# Project.net
KiCad netlist of a schematic drawn in Altium Designer
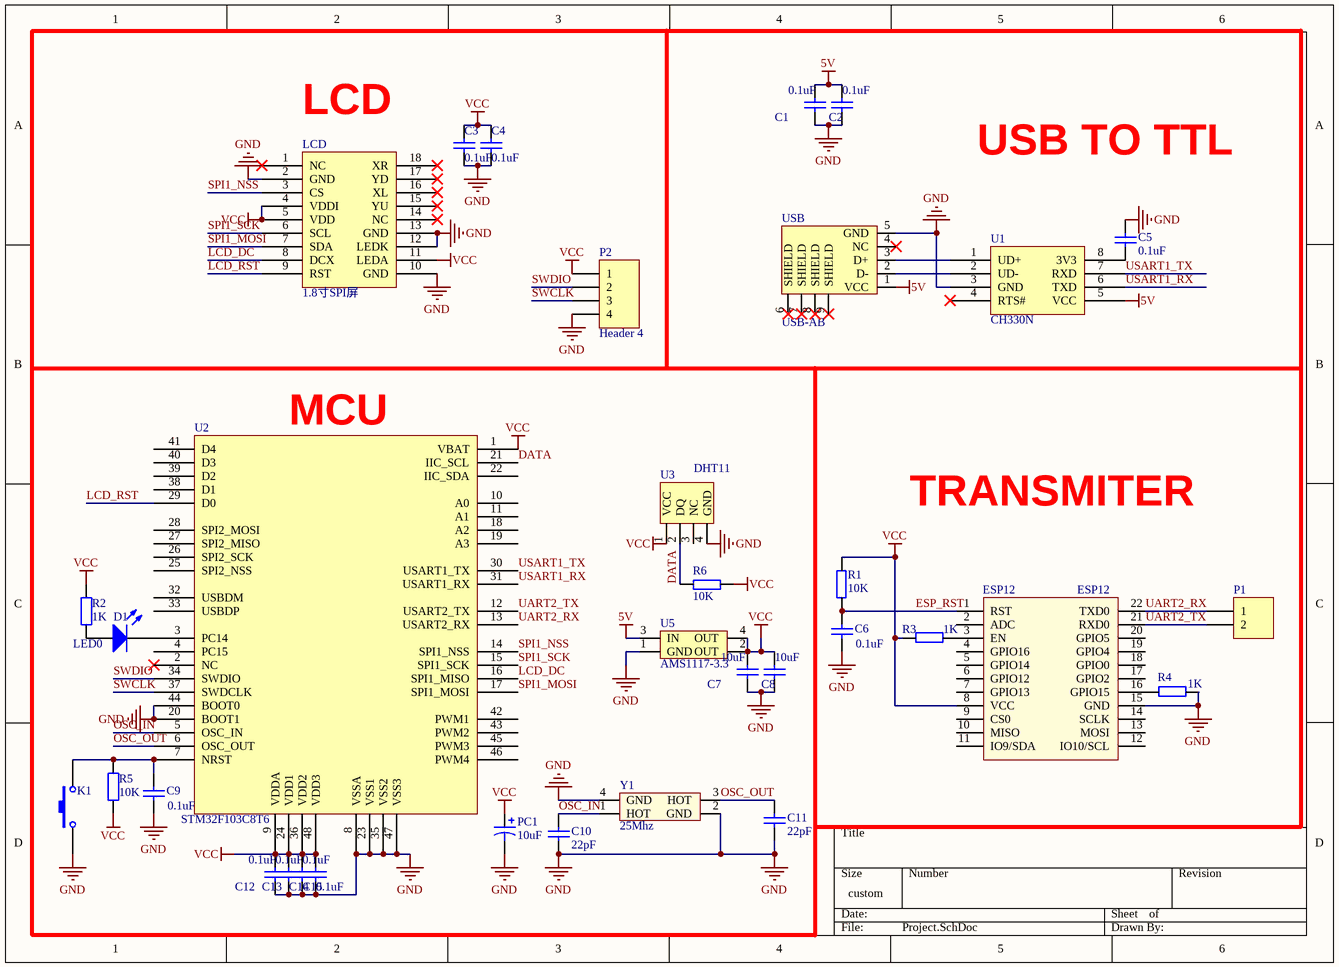
[diagram p0: Project.SchDoc]

(export (version "E")
  (design (tool "Eeschema 10.0.6"))
  (components
    (comp (ref "C1")
      (value "0.1uF")
      (footprint "0603P")
      (description "Capacitor")
      (fields (field (name "Comment") "Cap") (field (name "PUBLISHER") "Altium Limited"))
      (libsource (lib "Miscellaneous Devices") (part "Cap"))
    )
    (comp (ref "C2")
      (value "0.1uF")
      (footprint "0603P")
      (description "Capacitor")
      (fields (field (name "Comment") "Cap") (field (name "PUBLISHER") "Altium Limited"))
      (libsource (lib "Miscellaneous Devices") (part "Cap"))
    )
    (comp (ref "C3")
      (value "0.1uF")
      (footprint "1206")
      (description "Capacitor")
      (fields (field (name "Comment") "Cap") (field (name "PUBLISHER") "Altium Limited"))
      (libsource (lib "Miscellaneous Devices") (part "Cap"))
    )
    (comp (ref "C4")
      (value "0.1uF")
      (footprint "0603P")
      (description "Capacitor")
      (fields (field (name "Comment") "Cap") (field (name "PUBLISHER") "Altium Limited"))
      (libsource (lib "Miscellaneous Devices") (part "Cap"))
    )
    (comp (ref "C5")
      (value "0.1uF")
      (footprint "0603P")
      (description "Capacitor")
      (fields (field (name "Comment") "Cap") (field (name "PUBLISHER") "Altium Limited"))
      (libsource (lib "Miscellaneous Devices") (part "Cap"))
    )
    (comp (ref "C6")
      (value "0.1uF")
      (footprint "0603P")
      (description "Capacitor")
      (fields (field (name "Comment") "Cap") (field (name "PUBLISHER") "Altium Limited"))
      (libsource (lib "Miscellaneous Devices") (part "Cap"))
    )
    (comp (ref "C7")
      (value "10uF")
      (footprint "1206")
      (description "Capacitor")
      (fields (field (name "Comment") "Cap") (field (name "PUBLISHER") "Altium Limited"))
      (libsource (lib "Miscellaneous Devices") (part "Cap"))
    )
    (comp (ref "C8")
      (value "10uF")
      (footprint "1206")
      (description "Capacitor")
      (fields (field (name "Comment") "Cap") (field (name "PUBLISHER") "Altium Limited"))
      (libsource (lib "Miscellaneous Devices") (part "Cap"))
    )
    (comp (ref "C9")
      (value "0.1uF")
      (footprint "0603P")
      (description "Capacitor")
      (fields (field (name "Comment") "Cap") (field (name "PUBLISHER") "Altium Limited"))
      (libsource (lib "Miscellaneous Devices") (part "Cap"))
    )
    (comp (ref "C10")
      (value "22pF")
      (footprint "0603P")
      (description "Capacitor")
      (fields (field (name "Comment") "Cap") (field (name "PUBLISHER") "Altium Limited"))
      (libsource (lib "Miscellaneous Devices") (part "Cap"))
    )
    (comp (ref "C11")
      (value "22pF")
      (footprint "0603P")
      (description "Capacitor")
      (fields (field (name "Comment") "Cap") (field (name "PUBLISHER") "Altium Limited"))
      (libsource (lib "Miscellaneous Devices") (part "Cap"))
    )
    (comp (ref "C12")
      (value "0.1uF")
      (footprint "0603P")
      (description "Capacitor")
      (fields (field (name "Comment") "Cap") (field (name "PUBLISHER") "Altium Limited"))
      (libsource (lib "Miscellaneous Devices") (part "Cap"))
    )
    (comp (ref "C13")
      (value "0.1uF")
      (footprint "0603P")
      (description "Capacitor")
      (fields (field (name "Comment") "Cap") (field (name "PUBLISHER") "Altium Limited"))
      (libsource (lib "Miscellaneous Devices") (part "Cap"))
    )
    (comp (ref "C14")
      (value "0.1uF")
      (footprint "0603P")
      (description "Capacitor")
      (fields (field (name "Comment") "Cap") (field (name "PUBLISHER") "Altium Limited"))
      (libsource (lib "Miscellaneous Devices") (part "Cap"))
    )
    (comp (ref "C15")
      (value "0.1uF")
      (footprint "0603P")
      (description "Capacitor")
      (fields (field (name "Comment") "Cap") (field (name "PUBLISHER") "Altium Limited"))
      (libsource (lib "Miscellaneous Devices") (part "Cap"))
    )
    (comp (ref "D1")
      (value "LED0")
      (footprint "SMDLED-0603")
      (description "Typical INFRARED GaAs LED")
      (fields (field (name "PUBLISHER") "Altium Limited"))
      (libsource (lib "Miscellaneous Devices") (part "LED0"))
    )
    (comp (ref "ESP12")
      (value "ESP12")
      (footprint "ESP-12改后:ESP-12E&F Module")
      (description "ESP-12E&F Module")
      (libsource (lib "ESP-12改后") (part "ESP-12E&F Module"))
    )
    (comp (ref "K1")
      (value "KEY")
      (footprint "KEY_SOP3625")
      (description "Switch")
      (fields (field (name "PUBLISHER") "Altium Limited"))
      (libsource (lib "My Footprint") (part "KEY_2"))
    )
    (comp (ref "LCD")
      (value "1.8寸SPI屏")
      (footprint "FPC0.5 18Pin")
      (libsource (lib "常用元件") (part "1.8寸SPI屏"))
    )
    (comp (ref "P1")
      (value "Header 2")
      (footprint "HDR1X2")
      (description "Header, 2-Pin")
      (fields (field (name "PUBLISHER") "Altium Limited"))
      (libsource (lib "Miscellaneous Connectors") (part "Header 2"))
    )
    (comp (ref "P2")
      (value "Header 4")
      (footprint "HDR1X4")
      (description "Header, 4-Pin")
      (fields (field (name "PUBLISHER") "Altium Limited"))
      (libsource (lib "Miscellaneous Connectors") (part "Header 4"))
    )
    (comp (ref "PC1")
      (value "10uF")
      (footprint "1206")
      (description "Polarized Capacitor (Surface Mount)")
      (fields (field (name "PUBLISHER") "Altium Limited"))
      (libsource (lib "Miscellaneous Devices") (part "Cap Pol3"))
    )
    (comp (ref "R1") (value "10K") (footprint "0603P") (libsource (lib "STM32H743核心板封装库") (part "R")))
    (comp (ref "R2")
      (value "1K")
      (footprint "0603P")
      (description "Resistor")
      (fields (field (name "Comment") "Res2") (field (name "PUBLISHER") "Altium Limited"))
      (libsource (lib "") (part "Res2_1"))
    )
    (comp (ref "R3") (value "1K") (footprint "0603P") (libsource (lib "STM32H743核心板封装库") (part "R")))
    (comp (ref "R4") (value "1K") (footprint "0603P") (libsource (lib "STM32H743核心板封装库") (part "R")))
    (comp (ref "R5")
      (value "10K")
      (footprint "0603P")
      (description "Resistor")
      (fields (field (name "PUBLISHER") "Altium Limited"))
      (libsource (lib "Miscellaneous Devices") (part "Res2"))
    )
    (comp (ref "R6") (value "10K") (footprint "0603P") (libsource (lib "STM32H743核心板封装库") (part "R")))
    (comp (ref "U1") (value "CH330N") (footprint "sop8") (libsource (lib "常用元件") (part "CH330N")))
    (comp (ref "U2")
      (value "STM32F103C8T6")
      (footprint "LQFP-48")
      (libsource (lib "常用元件") (part "STM32F103C8T6"))
    )
    (comp (ref "U3")
      (value "DHT11")
      (footprint "DHT11")
      (description "数字温湿度传感器")
      (libsource (lib "阿波罗STM32F4&F7底板封装库") (part "DHT11"))
    )
    (comp (ref "U5")
      (value "AMS1117-3.3")
      (footprint "AMS1117")
      (libsource (lib "阿波罗STM32F4&F7底板封装库") (part "AMS1117"))
    )
    (comp (ref "USB")
      (value "USB-AB")
      (footprint "USB_AB")
      (description "MicroUSB")
      (libsource (lib "STM32F429核心板封装库") (part "USB-AB"))
    )
    (comp (ref "Y1")
      (value "25Mhz")
      (footprint "XTAL3225")
      (description "3225贴片无源晶振")
      (libsource (lib "STM32F429核心板封装库") (part "XTAL_3225"))
    )
  )
  (nets
    (net (code "1") (name "/DATA") (class "Default")
      (node (ref "R6") (pin "1") (pintype "passive"))
      (node (ref "U2") (pin "21") (pinfunction "IIC_SCL_21") (pintype "passive"))
      (node (ref "U3") (pin "2") (pinfunction "DQ_2") (pintype "passive"))
    )
    (net (code "2") (name "/ESP_RST") (class "Default")
      (node (ref "C6") (pin "2") (pinfunction "2_2") (pintype "passive"))
      (node (ref "ESP12") (pin "1") (pinfunction "RST_1") (pintype "passive"))
      (node (ref "R1") (pin "2") (pintype "passive"))
    )
    (net (code "3") (name "/LCD_DC") (class "Default")
      (node (ref "LCD") (pin "8") (pinfunction "DCX_8") (pintype "passive"))
      (node (ref "U2") (pin "16") (pinfunction "SPI1_MISO_16") (pintype "passive"))
    )
    (net (code "4") (name "/LCD_RST") (class "Default")
      (node (ref "LCD") (pin "9") (pinfunction "RST_9") (pintype "passive"))
      (node (ref "U2") (pin "29") (pinfunction "D0_29") (pintype "passive"))
    )
    (net (code "5") (name "/OSC_IN") (class "Default")
      (node (ref "C10") (pin "1") (pinfunction "1_1") (pintype "passive"))
      (node (ref "U2") (pin "5") (pinfunction "OSC_IN_5") (pintype "passive"))
      (node (ref "Y1") (pin "1") (pinfunction "HOT_1") (pintype "passive"))
    )
    (net (code "6") (name "/OSC_OUT") (class "Default")
      (node (ref "C11") (pin "1") (pinfunction "1_1") (pintype "passive"))
      (node (ref "U2") (pin "6") (pinfunction "OSC_OUT_6") (pintype "passive"))
      (node (ref "Y1") (pin "3") (pinfunction "HOT_3") (pintype "passive"))
    )
    (net (code "7") (name "/SPI1_MOSI") (class "Default")
      (node (ref "LCD") (pin "7") (pinfunction "SDA_7") (pintype "passive"))
      (node (ref "U2") (pin "17") (pinfunction "SPI1_MOSI_17") (pintype "passive"))
    )
    (net (code "8") (name "/SPI1_NSS") (class "Default")
      (node (ref "LCD") (pin "3") (pinfunction "CS_3") (pintype "passive"))
      (node (ref "U2") (pin "14") (pinfunction "SPI1_NSS_14") (pintype "passive"))
    )
    (net (code "9") (name "/SPI1_SCK") (class "Default")
      (node (ref "LCD") (pin "6") (pinfunction "SCL_6") (pintype "passive"))
      (node (ref "U2") (pin "15") (pinfunction "SPI1_SCK_15") (pintype "passive"))
    )
    (net (code "10") (name "/SWCLK") (class "Default")
      (node (ref "P2") (pin "3") (pinfunction "3_3") (pintype "passive"))
      (node (ref "U2") (pin "37") (pinfunction "SWDCLK_37") (pintype "passive"))
    )
    (net (code "11") (name "/SWDIO") (class "Default")
      (node (ref "P2") (pin "2") (pinfunction "2_2") (pintype "passive"))
      (node (ref "U2") (pin "34") (pinfunction "SWDIO_34") (pintype "passive"))
    )
    (net (code "12") (name "/UART2_RX") (class "Default")
      (node (ref "ESP12") (pin "22") (pinfunction "TXD0_22") (pintype "passive"))
      (node (ref "P1") (pin "1") (pinfunction "1_1") (pintype "passive"))
      (node (ref "U2") (pin "13") (pinfunction "USART2_RX_13") (pintype "passive"))
    )
    (net (code "13") (name "/UART2_TX") (class "Default")
      (node (ref "ESP12") (pin "21") (pinfunction "RXD0_21") (pintype "passive"))
      (node (ref "P1") (pin "2") (pinfunction "2_2") (pintype "passive"))
      (node (ref "U2") (pin "12") (pinfunction "USART2_TX_12") (pintype "passive"))
    )
    (net (code "14") (name "/USART1_RX") (class "Default")
      (node (ref "U1") (pin "6") (pinfunction "TXD_6") (pintype "passive"))
      (node (ref "U2") (pin "31") (pinfunction "USART1_RX_31") (pintype "passive"))
    )
    (net (code "15") (name "/USART1_TX") (class "Default")
      (node (ref "U1") (pin "7") (pinfunction "RXD_7") (pintype "passive"))
      (node (ref "U2") (pin "30") (pinfunction "USART1_TX_30") (pintype "passive"))
    )
    (net (code "16") (name "5V") (class "Default")
      (node (ref "C1") (pin "2") (pinfunction "2_2") (pintype "passive"))
      (node (ref "C2") (pin "2") (pinfunction "2_2") (pintype "passive"))
      (node (ref "U1") (pin "5") (pinfunction "VCC_5") (pintype "passive"))
      (node (ref "U5") (pin "3") (pinfunction "IN_3") (pintype "passive"))
      (node (ref "USB") (pin "1") (pinfunction "VCC_1") (pintype "passive"))
    )
    (net (code "17") (name "GND") (class "Default")
      (node (ref "C1") (pin "1") (pinfunction "1_1") (pintype "passive"))
      (node (ref "C10") (pin "2") (pinfunction "2_2") (pintype "passive"))
      (node (ref "C11") (pin "2") (pinfunction "2_2") (pintype "passive"))
      (node (ref "C12") (pin "1") (pinfunction "1_1") (pintype "passive"))
      (node (ref "C13") (pin "1") (pinfunction "1_1") (pintype "passive"))
      (node (ref "C14") (pin "1") (pinfunction "1_1") (pintype "passive"))
      (node (ref "C15") (pin "1") (pinfunction "1_1") (pintype "passive"))
      (node (ref "C2") (pin "1") (pinfunction "1_1") (pintype "passive"))
      (node (ref "C3") (pin "1") (pinfunction "1_1") (pintype "passive"))
      (node (ref "C4") (pin "1") (pinfunction "1_1") (pintype "passive"))
      (node (ref "C5") (pin "2") (pinfunction "2_2") (pintype "passive"))
      (node (ref "C6") (pin "1") (pinfunction "1_1") (pintype "passive"))
      (node (ref "C7") (pin "1") (pinfunction "1_1") (pintype "passive"))
      (node (ref "C8") (pin "1") (pinfunction "1_1") (pintype "passive"))
      (node (ref "C9") (pin "1") (pinfunction "1_1") (pintype "passive"))
      (node (ref "ESP12") (pin "15") (pinfunction "GND_15") (pintype "passive"))
      (node (ref "K1") (pin "1") (pinfunction "1_1") (pintype "passive"))
      (node (ref "LCD") (pin "10") (pinfunction "GND_10") (pintype "passive"))
      (node (ref "LCD") (pin "12") (pinfunction "LEDK_12") (pintype "passive"))
      (node (ref "LCD") (pin "13") (pinfunction "GND_13") (pintype "passive"))
      (node (ref "LCD") (pin "2") (pinfunction "GND_2") (pintype "passive"))
      (node (ref "P2") (pin "4") (pinfunction "4_4") (pintype "passive"))
      (node (ref "PC1") (pin "2") (pinfunction "2_2") (pintype "passive"))
      (node (ref "R4") (pin "1") (pintype "passive"))
      (node (ref "U1") (pin "3") (pinfunction "GND_3") (pintype "passive"))
      (node (ref "U2") (pin "20") (pinfunction "BOOT1_20") (pintype "passive"))
      (node (ref "U2") (pin "23") (pinfunction "VSS1_23") (pintype "passive"))
      (node (ref "U2") (pin "35") (pinfunction "VSS2_35") (pintype "passive"))
      (node (ref "U2") (pin "44") (pinfunction "BOOT0_44") (pintype "passive"))
      (node (ref "U2") (pin "47") (pinfunction "VSS3_47") (pintype "passive"))
      (node (ref "U2") (pin "8") (pinfunction "VSSA_8") (pintype "passive"))
      (node (ref "U3") (pin "4") (pinfunction "GND_4") (pintype "passive"))
      (node (ref "U5") (pin "1") (pinfunction "GND_1") (pintype "passive"))
      (node (ref "USB") (pin "5") (pinfunction "GND_5") (pintype "passive"))
      (node (ref "Y1") (pin "2") (pinfunction "GND_2") (pintype "passive"))
      (node (ref "Y1") (pin "4") (pinfunction "GND_4") (pintype "passive"))
    )
    (net (code "18") (name "Net-(D1-A)") (class "Default")
      (node (ref "D1") (pin "1") (pinfunction "A_1") (pintype "passive"))
      (node (ref "R2") (pin "2") (pinfunction "2_2") (pintype "passive"))
    )
    (net (code "19") (name "Net-(D1-K)") (class "Default")
      (node (ref "D1") (pin "2") (pinfunction "K_2") (pintype "passive"))
      (node (ref "U2") (pin "3") (pinfunction "PC14_3") (pintype "passive"))
    )
    (net (code "20") (name "Net-(ESP12-EN)") (class "Default")
      (node (ref "ESP12") (pin "3") (pinfunction "EN_3") (pintype "passive"))
      (node (ref "R3") (pin "1") (pintype "passive"))
    )
    (net (code "21") (name "Net-(ESP12-GPIO15)") (class "Default")
      (node (ref "ESP12") (pin "16") (pinfunction "GPIO15_16") (pintype "passive"))
      (node (ref "R4") (pin "2") (pintype "passive"))
    )
    (net (code "22") (name "Net-(U1-3V3)") (class "Default")
      (node (ref "C5") (pin "1") (pinfunction "1_1") (pintype "passive"))
      (node (ref "U1") (pin "8") (pinfunction "3V3_8") (pintype "passive"))
    )
    (net (code "23") (name "Net-(U1-UD+)") (class "Default")
      (node (ref "U1") (pin "1") (pinfunction "UD+_1") (pintype "passive"))
      (node (ref "USB") (pin "3") (pinfunction "D+_3") (pintype "passive"))
    )
    (net (code "24") (name "Net-(U1-UD-)") (class "Default")
      (node (ref "U1") (pin "2") (pinfunction "UD-_2") (pintype "passive"))
      (node (ref "USB") (pin "2") (pinfunction "D-_2") (pintype "passive"))
    )
    (net (code "25") (name "Net-(U2-NRST)") (class "Default")
      (node (ref "C9") (pin "2") (pinfunction "2_2") (pintype "passive"))
      (node (ref "K1") (pin "2") (pinfunction "2_2") (pintype "passive"))
      (node (ref "R5") (pin "2") (pinfunction "2_2") (pintype "passive"))
      (node (ref "U2") (pin "7") (pinfunction "NRST_7") (pintype "passive"))
    )
    (net (code "26") (name "VCC") (class "Default")
      (node (ref "C12") (pin "2") (pinfunction "2_2") (pintype "passive"))
      (node (ref "C13") (pin "2") (pinfunction "2_2") (pintype "passive"))
      (node (ref "C14") (pin "2") (pinfunction "2_2") (pintype "passive"))
      (node (ref "C15") (pin "2") (pinfunction "2_2") (pintype "passive"))
      (node (ref "C3") (pin "2") (pinfunction "2_2") (pintype "passive"))
      (node (ref "C4") (pin "2") (pinfunction "2_2") (pintype "passive"))
      (node (ref "C7") (pin "2") (pinfunction "2_2") (pintype "passive"))
      (node (ref "C8") (pin "2") (pinfunction "2_2") (pintype "passive"))
      (node (ref "ESP12") (pin "8") (pinfunction "VCC_8") (pintype "passive"))
      (node (ref "LCD") (pin "11") (pinfunction "LEDA_11") (pintype "passive"))
      (node (ref "LCD") (pin "4") (pinfunction "VDDI_4") (pintype "passive"))
      (node (ref "LCD") (pin "5") (pinfunction "VDD_5") (pintype "passive"))
      (node (ref "P2") (pin "1") (pinfunction "1_1") (pintype "passive"))
      (node (ref "PC1") (pin "1") (pinfunction "1_1") (pintype "passive"))
      (node (ref "R1") (pin "1") (pintype "passive"))
      (node (ref "R2") (pin "1") (pinfunction "1_1") (pintype "passive"))
      (node (ref "R3") (pin "2") (pintype "passive"))
      (node (ref "R5") (pin "1") (pinfunction "1_1") (pintype "passive"))
      (node (ref "R6") (pin "2") (pintype "passive"))
      (node (ref "U2") (pin "1") (pinfunction "VBAT_1") (pintype "passive"))
      (node (ref "U2") (pin "24") (pinfunction "VDD1_24") (pintype "passive"))
      (node (ref "U2") (pin "36") (pinfunction "VDD2_36") (pintype "passive"))
      (node (ref "U2") (pin "48") (pinfunction "VDD3_48") (pintype "passive"))
      (node (ref "U2") (pin "9") (pinfunction "VDDA_9") (pintype "passive"))
      (node (ref "U3") (pin "1") (pinfunction "VCC_1") (pintype "passive"))
      (node (ref "U5") (pin "2") (pinfunction "OUT_2") (pintype "passive"))
      (node (ref "U5") (pin "4") (pinfunction "OUT_4") (pintype "passive"))
    )
    (net (code "27") (name "unconnected-(ESP12-ADC-Pad2)") (class "Default")
      (node (ref "ESP12") (pin "2") (pinfunction "ADC_2") (pintype "passive"))
    )
    (net (code "28") (name "unconnected-(ESP12-CS0-Pad9)") (class "Default")
      (node (ref "ESP12") (pin "9") (pinfunction "CS0_9") (pintype "passive"))
    )
    (net (code "29") (name "unconnected-(ESP12-GPIO0-Pad18)") (class "Default")
      (node (ref "ESP12") (pin "18") (pinfunction "GPIO0_18") (pintype "passive"))
    )
    (net (code "30") (name "unconnected-(ESP12-GPIO2-Pad17)") (class "Default")
      (node (ref "ESP12") (pin "17") (pinfunction "GPIO2_17") (pintype "passive"))
    )
    (net (code "31") (name "unconnected-(ESP12-GPIO4-Pad19)") (class "Default")
      (node (ref "ESP12") (pin "19") (pinfunction "GPIO4_19") (pintype "passive"))
    )
    (net (code "32") (name "unconnected-(ESP12-GPIO5-Pad20)") (class "Default")
      (node (ref "ESP12") (pin "20") (pinfunction "GPIO5_20") (pintype "passive"))
    )
    (net (code "33") (name "unconnected-(ESP12-GPIO12-Pad6)") (class "Default")
      (node (ref "ESP12") (pin "6") (pinfunction "GPIO12_6") (pintype "passive"))
    )
    (net (code "34") (name "unconnected-(ESP12-GPIO13-Pad7)") (class "Default")
      (node (ref "ESP12") (pin "7") (pinfunction "GPIO13_7") (pintype "passive"))
    )
    (net (code "35") (name "unconnected-(ESP12-GPIO14-Pad5)") (class "Default")
      (node (ref "ESP12") (pin "5") (pinfunction "GPIO14_5") (pintype "passive"))
    )
    (net (code "36") (name "unconnected-(ESP12-GPIO16-Pad4)") (class "Default")
      (node (ref "ESP12") (pin "4") (pinfunction "GPIO16_4") (pintype "passive"))
    )
    (net (code "37") (name "unconnected-(ESP12-IO9{slash}SDA-Pad11)") (class "Default")
      (node (ref "ESP12") (pin "11") (pinfunction "IO9/SDA_11") (pintype "passive"))
    )
    (net (code "38") (name "unconnected-(ESP12-IO10{slash}SCL-Pad12)") (class "Default")
      (node (ref "ESP12") (pin "12") (pinfunction "IO10/SCL_12") (pintype "passive"))
    )
    (net (code "39") (name "unconnected-(ESP12-MISO-Pad10)") (class "Default")
      (node (ref "ESP12") (pin "10") (pinfunction "MISO_10") (pintype "passive"))
    )
    (net (code "40") (name "unconnected-(ESP12-MOSI-Pad13)") (class "Default")
      (node (ref "ESP12") (pin "13") (pinfunction "MOSI_13") (pintype "passive"))
    )
    (net (code "41") (name "unconnected-(ESP12-SCLK-Pad14)") (class "Default")
      (node (ref "ESP12") (pin "14") (pinfunction "SCLK_14") (pintype "passive"))
    )
    (net (code "42") (name "unconnected-(LCD-NC-Pad1)") (class "Default")
      (node (ref "LCD") (pin "1") (pinfunction "NC_1") (pintype "passive+no_connect"))
    )
    (net (code "43") (name "unconnected-(LCD-NC-Pad14)") (class "Default")
      (node (ref "LCD") (pin "14") (pinfunction "NC_14") (pintype "passive+no_connect"))
    )
    (net (code "44") (name "unconnected-(LCD-XL-Pad16)") (class "Default")
      (node (ref "LCD") (pin "16") (pinfunction "XL_16") (pintype "passive+no_connect"))
    )
    (net (code "45") (name "unconnected-(LCD-XR-Pad18)") (class "Default")
      (node (ref "LCD") (pin "18") (pinfunction "XR_18") (pintype "passive+no_connect"))
    )
    (net (code "46") (name "unconnected-(LCD-YD-Pad17)") (class "Default")
      (node (ref "LCD") (pin "17") (pinfunction "YD_17") (pintype "passive+no_connect"))
    )
    (net (code "47") (name "unconnected-(LCD-YU-Pad15)") (class "Default")
      (node (ref "LCD") (pin "15") (pinfunction "YU_15") (pintype "passive+no_connect"))
    )
    (net (code "48") (name "unconnected-(U1-RTS#-Pad4)") (class "Default")
      (node (ref "U1") (pin "4") (pinfunction "RTS#_4") (pintype "passive+no_connect"))
    )
    (net (code "49") (name "unconnected-(U2-A0-Pad10)") (class "Default")
      (node (ref "U2") (pin "10") (pinfunction "A0_10") (pintype "passive"))
    )
    (net (code "50") (name "unconnected-(U2-A1-Pad11)") (class "Default")
      (node (ref "U2") (pin "11") (pinfunction "A1_11") (pintype "passive"))
    )
    (net (code "51") (name "unconnected-(U2-A2-Pad18)") (class "Default")
      (node (ref "U2") (pin "18") (pinfunction "A2_18") (pintype "passive"))
    )
    (net (code "52") (name "unconnected-(U2-A3-Pad19)") (class "Default")
      (node (ref "U2") (pin "19") (pinfunction "A3_19") (pintype "passive"))
    )
    (net (code "53") (name "unconnected-(U2-D1-Pad38)") (class "Default")
      (node (ref "U2") (pin "38") (pinfunction "D1_38") (pintype "passive"))
    )
    (net (code "54") (name "unconnected-(U2-D2-Pad39)") (class "Default")
      (node (ref "U2") (pin "39") (pinfunction "D2_39") (pintype "passive"))
    )
    (net (code "55") (name "unconnected-(U2-D3-Pad40)") (class "Default")
      (node (ref "U2") (pin "40") (pinfunction "D3_40") (pintype "passive"))
    )
    (net (code "56") (name "unconnected-(U2-D4-Pad41)") (class "Default")
      (node (ref "U2") (pin "41") (pinfunction "D4_41") (pintype "passive"))
    )
    (net (code "57") (name "unconnected-(U2-IIC_SDA-Pad22)") (class "Default")
      (node (ref "U2") (pin "22") (pinfunction "IIC_SDA_22") (pintype "passive"))
    )
    (net (code "58") (name "unconnected-(U2-NC-Pad2)") (class "Default")
      (node (ref "U2") (pin "2") (pinfunction "NC_2") (pintype "passive+no_connect"))
    )
    (net (code "59") (name "unconnected-(U2-PC15-Pad4)") (class "Default")
      (node (ref "U2") (pin "4") (pinfunction "PC15_4") (pintype "passive"))
    )
    (net (code "60") (name "unconnected-(U2-PWM1-Pad42)") (class "Default")
      (node (ref "U2") (pin "42") (pinfunction "PWM1_42") (pintype "passive"))
    )
    (net (code "61") (name "unconnected-(U2-PWM2-Pad43)") (class "Default")
      (node (ref "U2") (pin "43") (pinfunction "PWM2_43") (pintype "passive"))
    )
    (net (code "62") (name "unconnected-(U2-PWM3-Pad45)") (class "Default")
      (node (ref "U2") (pin "45") (pinfunction "PWM3_45") (pintype "passive"))
    )
    (net (code "63") (name "unconnected-(U2-PWM4-Pad46)") (class "Default")
      (node (ref "U2") (pin "46") (pinfunction "PWM4_46") (pintype "passive"))
    )
    (net (code "64") (name "unconnected-(U2-SPI2_MISO-Pad27)") (class "Default")
      (node (ref "U2") (pin "27") (pinfunction "SPI2_MISO_27") (pintype "passive"))
    )
    (net (code "65") (name "unconnected-(U2-SPI2_MOSI-Pad28)") (class "Default")
      (node (ref "U2") (pin "28") (pinfunction "SPI2_MOSI_28") (pintype "passive"))
    )
    (net (code "66") (name "unconnected-(U2-SPI2_NSS-Pad25)") (class "Default")
      (node (ref "U2") (pin "25") (pinfunction "SPI2_NSS_25") (pintype "passive"))
    )
    (net (code "67") (name "unconnected-(U2-SPI2_SCK-Pad26)") (class "Default")
      (node (ref "U2") (pin "26") (pinfunction "SPI2_SCK_26") (pintype "passive"))
    )
    (net (code "68") (name "unconnected-(U2-USBDM-Pad32)") (class "Default")
      (node (ref "U2") (pin "32") (pinfunction "USBDM_32") (pintype "passive"))
    )
    (net (code "69") (name "unconnected-(U2-USBDP-Pad33)") (class "Default")
      (node (ref "U2") (pin "33") (pinfunction "USBDP_33") (pintype "passive"))
    )
    (net (code "70") (name "unconnected-(U3-NC-Pad3)") (class "Default")
      (node (ref "U3") (pin "3") (pinfunction "NC_3") (pintype "passive"))
    )
    (net (code "71") (name "unconnected-(USB-NC-Pad4)") (class "Default")
      (node (ref "USB") (pin "4") (pinfunction "NC_4") (pintype "passive+no_connect"))
    )
    (net (code "72") (name "unconnected-(USB-SHIELD-Pad6)") (class "Default")
      (node (ref "USB") (pin "6") (pinfunction "SHIELD_6") (pintype "passive+no_connect"))
    )
    (net (code "73") (name "unconnected-(USB-SHIELD-Pad7)") (class "Default")
      (node (ref "USB") (pin "7") (pinfunction "SHIELD_7") (pintype "passive+no_connect"))
    )
    (net (code "74") (name "unconnected-(USB-SHIELD-Pad8)") (class "Default")
      (node (ref "USB") (pin "8") (pinfunction "SHIELD_8") (pintype "passive+no_connect"))
    )
    (net (code "75") (name "unconnected-(USB-SHIELD-Pad9)") (class "Default")
      (node (ref "USB") (pin "9") (pinfunction "SHIELD_9") (pintype "passive+no_connect"))
    )
  )
)
